# raspi.net
KiCad netlist of a schematic drawn in Altium Designer
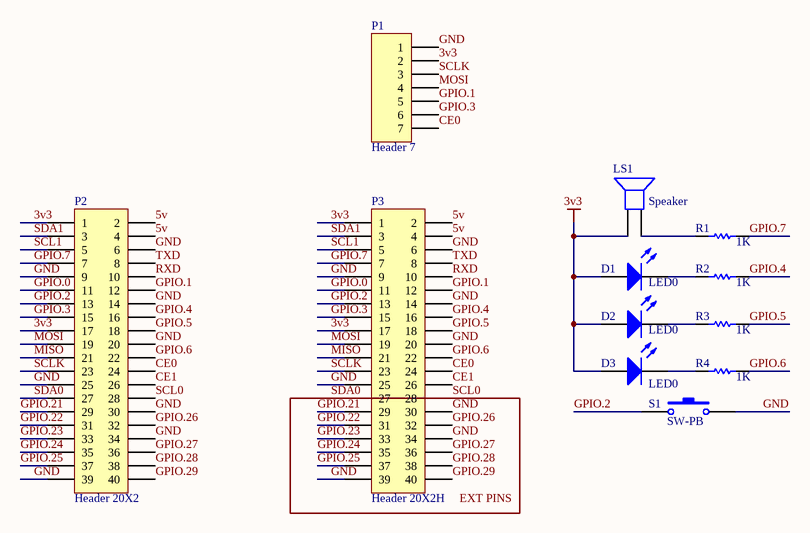
[diagram p0: raspi.SchDoc]

(export (version "E")
  (design (tool "Eeschema 10.0.6"))
  (components
    (comp (ref "D1")
      (value "LED0")
      (footprint "LED-0")
      (description "Typical INFRARED GaAs LED")
      (fields (field (name "PUBLISHER") "Altium Limited"))
      (libsource (lib "Miscellaneous Devices") (part "LED0"))
    )
    (comp (ref "D2")
      (value "LED0")
      (footprint "LED-0")
      (description "Typical INFRARED GaAs LED")
      (fields (field (name "PUBLISHER") "Altium Limited"))
      (libsource (lib "Miscellaneous Devices") (part "LED0"))
    )
    (comp (ref "D3")
      (value "LED0")
      (footprint "LED-0")
      (description "Typical INFRARED GaAs LED")
      (fields (field (name "PUBLISHER") "Altium Limited"))
      (libsource (lib "Miscellaneous Devices") (part "LED0"))
    )
    (comp (ref "LS1")
      (value "Speaker")
      (footprint "PIN2")
      (description "Loudspeaker")
      (fields (field (name "PUBLISHER") "Altium Limited"))
      (libsource (lib "Miscellaneous Devices") (part "Speaker"))
    )
    (comp (ref "P1")
      (value "Header 7")
      (footprint "HDR1X7")
      (description "Header, 7-Pin")
      (fields (field (name "PUBLISHER") "Altium Limited"))
      (libsource (lib "Miscellaneous Connectors") (part "Header 7"))
    )
    (comp (ref "P2")
      (value "Header 20X2")
      (footprint "HDR2X20")
      (description "Header, 20-Pin, Dual row")
      (fields (field (name "PUBLISHER") "Altium Limited"))
      (libsource (lib "Miscellaneous Connectors") (part "Header 20X2"))
    )
    (comp (ref "P3")
      (value "Header 20X2H")
      (footprint "HDR2X20H")
      (description "Header, 20-Pin, Dual row, Right Angle")
      (fields (field (name "PUBLISHER") "Altium Limited"))
      (libsource (lib "Miscellaneous Connectors") (part "Header 20X2H"))
    )
    (comp (ref "R1")
      (value "1K")
      (footprint "AXIAL-0.3")
      (description "Resistor")
      (fields (field (name "Comment") "Res1") (field (name "PUBLISHER") "Altium Limited"))
      (libsource (lib "Miscellaneous Devices") (part "Res1"))
    )
    (comp (ref "R2")
      (value "1K")
      (footprint "AXIAL-0.3")
      (description "Resistor")
      (fields (field (name "Comment") "Res1") (field (name "PUBLISHER") "Altium Limited"))
      (libsource (lib "Miscellaneous Devices") (part "Res1"))
    )
    (comp (ref "R3")
      (value "1K")
      (footprint "AXIAL-0.3")
      (description "Resistor")
      (fields (field (name "Comment") "Res1") (field (name "PUBLISHER") "Altium Limited"))
      (libsource (lib "Miscellaneous Devices") (part "Res1"))
    )
    (comp (ref "R4")
      (value "1K")
      (footprint "AXIAL-0.3")
      (description "Resistor")
      (fields (field (name "Comment") "Res1") (field (name "PUBLISHER") "Altium Limited"))
      (libsource (lib "Miscellaneous Devices") (part "Res1"))
    )
    (comp (ref "S1")
      (value "SW-PB")
      (footprint "SPST-2")
      (description "Switch")
      (fields (field (name "PUBLISHER") "Altium Limited"))
      (libsource (lib "Miscellaneous Devices") (part "SW-PB"))
    )
  )
  (nets
    (net (code "1") (name "/5v") (class "Default")
      (node (ref "P2") (pin "2") (pinfunction "2_2") (pintype "passive"))
      (node (ref "P2") (pin "4") (pinfunction "4_4") (pintype "passive"))
      (node (ref "P3") (pin "2") (pinfunction "2_2") (pintype "passive"))
      (node (ref "P3") (pin "4") (pinfunction "4_4") (pintype "passive"))
    )
    (net (code "2") (name "/CE0") (class "Default")
      (node (ref "P1") (pin "7") (pinfunction "7_7") (pintype "passive"))
      (node (ref "P2") (pin "24") (pinfunction "24_24") (pintype "passive"))
      (node (ref "P3") (pin "24") (pinfunction "24_24") (pintype "passive"))
    )
    (net (code "3") (name "/CE1") (class "Default")
      (node (ref "P2") (pin "26") (pinfunction "26_26") (pintype "passive"))
      (node (ref "P3") (pin "26") (pinfunction "26_26") (pintype "passive"))
    )
    (net (code "4") (name "/GND") (class "Default")
      (node (ref "P1") (pin "1") (pinfunction "1_1") (pintype "passive"))
      (node (ref "P2") (pin "14") (pinfunction "14_14") (pintype "passive"))
      (node (ref "P2") (pin "20") (pinfunction "20_20") (pintype "passive"))
      (node (ref "P2") (pin "25") (pinfunction "25_25") (pintype "passive"))
      (node (ref "P2") (pin "30") (pinfunction "30_30") (pintype "passive"))
      (node (ref "P2") (pin "34") (pinfunction "34_34") (pintype "passive"))
      (node (ref "P2") (pin "39") (pinfunction "39_39") (pintype "passive"))
      (node (ref "P2") (pin "6") (pinfunction "6_6") (pintype "passive"))
      (node (ref "P2") (pin "9") (pinfunction "9_9") (pintype "passive"))
      (node (ref "P3") (pin "14") (pinfunction "14_14") (pintype "passive"))
      (node (ref "P3") (pin "20") (pinfunction "20_20") (pintype "passive"))
      (node (ref "P3") (pin "25") (pinfunction "25_25") (pintype "passive"))
      (node (ref "P3") (pin "30") (pinfunction "30_30") (pintype "passive"))
      (node (ref "P3") (pin "34") (pinfunction "34_34") (pintype "passive"))
      (node (ref "P3") (pin "39") (pinfunction "39_39") (pintype "passive"))
      (node (ref "P3") (pin "6") (pinfunction "6_6") (pintype "passive"))
      (node (ref "P3") (pin "9") (pinfunction "9_9") (pintype "passive"))
      (node (ref "S1") (pin "2") (pinfunction "2_2") (pintype "passive"))
    )
    (net (code "5") (name "/GPIO.0") (class "Default")
      (node (ref "P2") (pin "11") (pinfunction "11_11") (pintype "passive"))
      (node (ref "P3") (pin "11") (pinfunction "11_11") (pintype "passive"))
    )
    (net (code "6") (name "/GPIO.1") (class "Default")
      (node (ref "P1") (pin "5") (pinfunction "5_5") (pintype "passive"))
      (node (ref "P2") (pin "12") (pinfunction "12_12") (pintype "passive"))
      (node (ref "P3") (pin "12") (pinfunction "12_12") (pintype "passive"))
    )
    (net (code "7") (name "/GPIO.2") (class "Default")
      (node (ref "P2") (pin "13") (pinfunction "13_13") (pintype "passive"))
      (node (ref "P3") (pin "13") (pinfunction "13_13") (pintype "passive"))
      (node (ref "S1") (pin "1") (pinfunction "1_1") (pintype "passive"))
    )
    (net (code "8") (name "/GPIO.3") (class "Default")
      (node (ref "P1") (pin "6") (pinfunction "6_6") (pintype "passive"))
      (node (ref "P2") (pin "15") (pinfunction "15_15") (pintype "passive"))
      (node (ref "P3") (pin "15") (pinfunction "15_15") (pintype "passive"))
    )
    (net (code "9") (name "/GPIO.4") (class "Default")
      (node (ref "P2") (pin "16") (pinfunction "16_16") (pintype "passive"))
      (node (ref "P3") (pin "16") (pinfunction "16_16") (pintype "passive"))
      (node (ref "R2") (pin "2") (pinfunction "2_2") (pintype "passive"))
    )
    (net (code "10") (name "/GPIO.5") (class "Default")
      (node (ref "P2") (pin "18") (pinfunction "18_18") (pintype "passive"))
      (node (ref "P3") (pin "18") (pinfunction "18_18") (pintype "passive"))
      (node (ref "R3") (pin "2") (pinfunction "2_2") (pintype "passive"))
    )
    (net (code "11") (name "/GPIO.6") (class "Default")
      (node (ref "P2") (pin "22") (pinfunction "22_22") (pintype "passive"))
      (node (ref "P3") (pin "22") (pinfunction "22_22") (pintype "passive"))
      (node (ref "R4") (pin "2") (pinfunction "2_2") (pintype "passive"))
    )
    (net (code "12") (name "/GPIO.7") (class "Default")
      (node (ref "P2") (pin "7") (pinfunction "7_7") (pintype "passive"))
      (node (ref "P3") (pin "7") (pinfunction "7_7") (pintype "passive"))
      (node (ref "R1") (pin "2") (pinfunction "2_2") (pintype "passive"))
    )
    (net (code "13") (name "/GPIO.21") (class "Default")
      (node (ref "P2") (pin "29") (pinfunction "29_29") (pintype "passive"))
      (node (ref "P3") (pin "29") (pinfunction "29_29") (pintype "passive"))
    )
    (net (code "14") (name "/GPIO.22") (class "Default")
      (node (ref "P2") (pin "31") (pinfunction "31_31") (pintype "passive"))
      (node (ref "P3") (pin "31") (pinfunction "31_31") (pintype "passive"))
    )
    (net (code "15") (name "/GPIO.23") (class "Default")
      (node (ref "P2") (pin "33") (pinfunction "33_33") (pintype "passive"))
      (node (ref "P3") (pin "33") (pinfunction "33_33") (pintype "passive"))
    )
    (net (code "16") (name "/GPIO.24") (class "Default")
      (node (ref "P2") (pin "35") (pinfunction "35_35") (pintype "passive"))
      (node (ref "P3") (pin "35") (pinfunction "35_35") (pintype "passive"))
    )
    (net (code "17") (name "/GPIO.25") (class "Default")
      (node (ref "P2") (pin "37") (pinfunction "37_37") (pintype "passive"))
      (node (ref "P3") (pin "37") (pinfunction "37_37") (pintype "passive"))
    )
    (net (code "18") (name "/GPIO.26") (class "Default")
      (node (ref "P2") (pin "32") (pinfunction "32_32") (pintype "passive"))
      (node (ref "P3") (pin "32") (pinfunction "32_32") (pintype "passive"))
    )
    (net (code "19") (name "/GPIO.27") (class "Default")
      (node (ref "P2") (pin "36") (pinfunction "36_36") (pintype "passive"))
      (node (ref "P3") (pin "36") (pinfunction "36_36") (pintype "passive"))
    )
    (net (code "20") (name "/GPIO.28") (class "Default")
      (node (ref "P2") (pin "38") (pinfunction "38_38") (pintype "passive"))
      (node (ref "P3") (pin "38") (pinfunction "38_38") (pintype "passive"))
    )
    (net (code "21") (name "/GPIO.29") (class "Default")
      (node (ref "P2") (pin "40") (pinfunction "40_40") (pintype "passive"))
      (node (ref "P3") (pin "40") (pinfunction "40_40") (pintype "passive"))
    )
    (net (code "22") (name "/MISO") (class "Default")
      (node (ref "P2") (pin "21") (pinfunction "21_21") (pintype "passive"))
      (node (ref "P3") (pin "21") (pinfunction "21_21") (pintype "passive"))
    )
    (net (code "23") (name "/MOSI") (class "Default")
      (node (ref "P1") (pin "4") (pinfunction "4_4") (pintype "passive"))
      (node (ref "P2") (pin "19") (pinfunction "19_19") (pintype "passive"))
      (node (ref "P3") (pin "19") (pinfunction "19_19") (pintype "passive"))
    )
    (net (code "24") (name "/RXD") (class "Default")
      (node (ref "P2") (pin "10") (pinfunction "10_10") (pintype "passive"))
      (node (ref "P3") (pin "10") (pinfunction "10_10") (pintype "passive"))
    )
    (net (code "25") (name "/SCL0") (class "Default")
      (node (ref "P2") (pin "28") (pinfunction "28_28") (pintype "passive"))
      (node (ref "P3") (pin "28") (pinfunction "28_28") (pintype "passive"))
    )
    (net (code "26") (name "/SCL1") (class "Default")
      (node (ref "P2") (pin "5") (pinfunction "5_5") (pintype "passive"))
      (node (ref "P3") (pin "5") (pinfunction "5_5") (pintype "passive"))
    )
    (net (code "27") (name "/SCLK") (class "Default")
      (node (ref "P1") (pin "3") (pinfunction "3_3") (pintype "passive"))
      (node (ref "P2") (pin "23") (pinfunction "23_23") (pintype "passive"))
      (node (ref "P3") (pin "23") (pinfunction "23_23") (pintype "passive"))
    )
    (net (code "28") (name "/SDA0") (class "Default")
      (node (ref "P2") (pin "27") (pinfunction "27_27") (pintype "passive"))
      (node (ref "P3") (pin "27") (pinfunction "27_27") (pintype "passive"))
    )
    (net (code "29") (name "/SDA1") (class "Default")
      (node (ref "P2") (pin "3") (pinfunction "3_3") (pintype "passive"))
      (node (ref "P3") (pin "3") (pinfunction "3_3") (pintype "passive"))
    )
    (net (code "30") (name "/TXD") (class "Default")
      (node (ref "P2") (pin "8") (pinfunction "8_8") (pintype "passive"))
      (node (ref "P3") (pin "8") (pinfunction "8_8") (pintype "passive"))
    )
    (net (code "31") (name "3v3") (class "Default")
      (node (ref "D1") (pin "1") (pinfunction "A_1") (pintype "passive"))
      (node (ref "D2") (pin "1") (pinfunction "A_1") (pintype "passive"))
      (node (ref "D3") (pin "1") (pinfunction "A_1") (pintype "passive"))
      (node (ref "LS1") (pin "1") (pinfunction "1_1") (pintype "passive"))
      (node (ref "P1") (pin "2") (pinfunction "2_2") (pintype "passive"))
      (node (ref "P2") (pin "1") (pinfunction "1_1") (pintype "passive"))
      (node (ref "P2") (pin "17") (pinfunction "17_17") (pintype "passive"))
      (node (ref "P3") (pin "1") (pinfunction "1_1") (pintype "passive"))
      (node (ref "P3") (pin "17") (pinfunction "17_17") (pintype "passive"))
    )
    (net (code "32") (name "Net-(D1-K)") (class "Default")
      (node (ref "D1") (pin "2") (pinfunction "K_2") (pintype "passive"))
      (node (ref "R2") (pin "1") (pinfunction "1_1") (pintype "passive"))
    )
    (net (code "33") (name "Net-(D2-K)") (class "Default")
      (node (ref "D2") (pin "2") (pinfunction "K_2") (pintype "passive"))
      (node (ref "R3") (pin "1") (pinfunction "1_1") (pintype "passive"))
    )
    (net (code "34") (name "Net-(D3-K)") (class "Default")
      (node (ref "D3") (pin "2") (pinfunction "K_2") (pintype "passive"))
      (node (ref "R4") (pin "1") (pinfunction "1_1") (pintype "passive"))
    )
    (net (code "35") (name "Net-(LS1-Pad2)") (class "Default")
      (node (ref "LS1") (pin "2") (pinfunction "2_2") (pintype "passive"))
      (node (ref "R1") (pin "1") (pinfunction "1_1") (pintype "passive"))
    )
  )
)
